# hall_sensor_final_displayv5.net
KiCad netlist of a schematic drawn in EAGLE
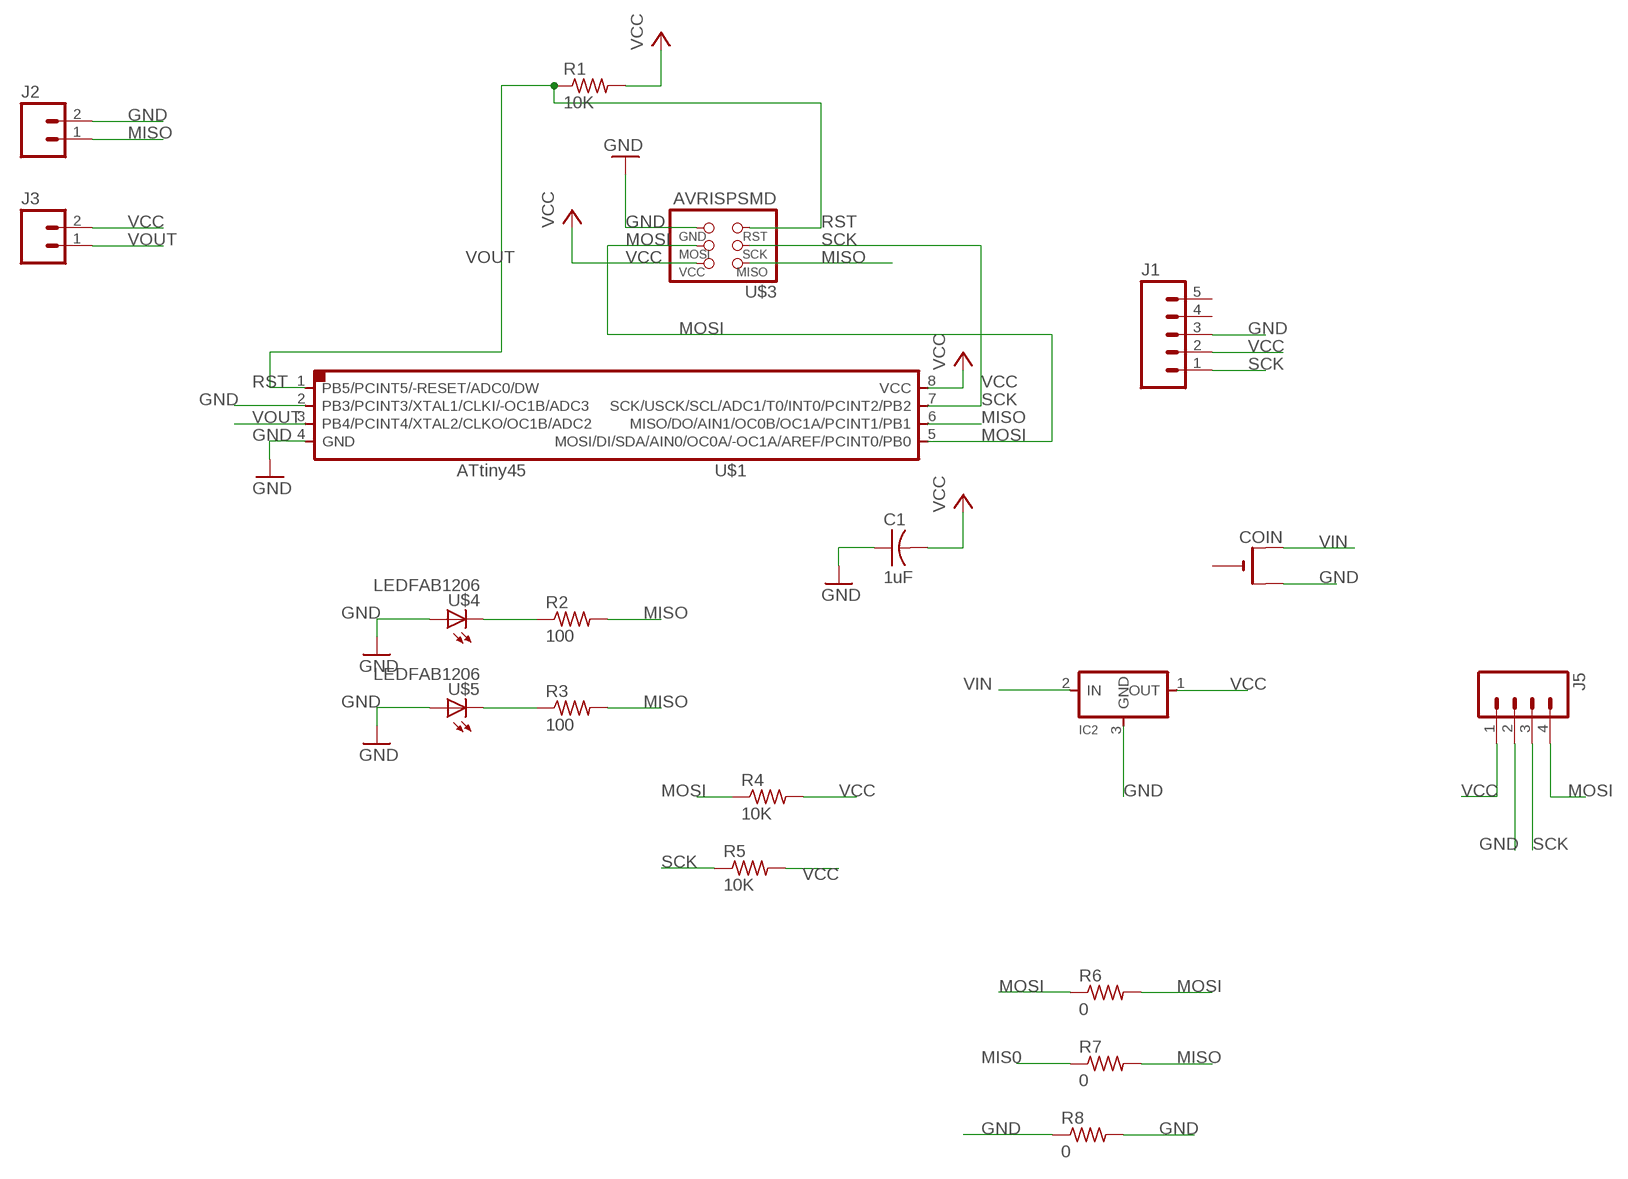
[diagram p0: schematic, sheet 1]

(export (version "E")
  (design (tool "Eeschema 10.0.6"))
  (components
    (comp (ref "C1")
      (value "1uF")
      (footprint "eagle-import:C1206FAB")
      (libsource (lib "eagle-import") (part "CAP-US1206FAB"))
    )
    (comp (ref "COIN")
      (value "CR2032THM")
      (footprint "eagle-import:CR2032-THRU")
      (libsource (lib "eagle-import") (part "CR2032THM"))
    )
    (comp (ref "IC2")
      (value "REGULATORSOT23")
      (footprint "eagle-import:SOT23")
      (libsource (lib "eagle-import") (part "REGULATORSOT23"))
    )
    (comp (ref "J1")
      (value "M05LOCK")
      (footprint "eagle-import:1X05_LOCK")
      (libsource (lib "eagle-import") (part "M05LOCK"))
    )
    (comp (ref "J2")
      (value "M02POLAR_LOCK")
      (footprint "eagle-import:MOLEX-1X2_LOCK")
      (libsource (lib "eagle-import") (part "M02POLAR_LOCK"))
    )
    (comp (ref "J3")
      (value "M02POLAR_LOCK")
      (footprint "eagle-import:MOLEX-1X2_LOCK")
      (libsource (lib "eagle-import") (part "M02POLAR_LOCK"))
    )
    (comp (ref "J5")
      (value "M04LOCK")
      (footprint "eagle-import:1X04_LOCK")
      (libsource (lib "eagle-import") (part "M04LOCK"))
    )
    (comp (ref "R1")
      (value "10K")
      (footprint "eagle-import:R1206FAB")
      (libsource (lib "eagle-import") (part "RES-US1206FAB"))
    )
    (comp (ref "R2")
      (value "100")
      (footprint "eagle-import:R1206FAB")
      (libsource (lib "eagle-import") (part "RES-US1206FAB"))
    )
    (comp (ref "R3")
      (value "100")
      (footprint "eagle-import:R1206FAB")
      (libsource (lib "eagle-import") (part "RES-US1206FAB"))
    )
    (comp (ref "R4")
      (value "10K")
      (footprint "eagle-import:R1206FAB")
      (libsource (lib "eagle-import") (part "RES-US1206FAB"))
    )
    (comp (ref "R5")
      (value "10K")
      (footprint "eagle-import:R1206FAB")
      (libsource (lib "eagle-import") (part "RES-US1206FAB"))
    )
    (comp (ref "R6")
      (value "0")
      (footprint "eagle-import:R1206FAB")
      (libsource (lib "eagle-import") (part "RES-US1206FAB"))
    )
    (comp (ref "R7")
      (value "0")
      (footprint "eagle-import:R1206FAB")
      (libsource (lib "eagle-import") (part "RES-US1206FAB"))
    )
    (comp (ref "R8")
      (value "0")
      (footprint "eagle-import:R1206FAB")
      (libsource (lib "eagle-import") (part "RES-US1206FAB"))
    )
    (comp (ref "U$1")
      (value "ATTINY45SI")
      (footprint "eagle-import:SOIC8")
      (libsource (lib "eagle-import") (part "ATTINY45SI"))
    )
    (comp (ref "U$3")
      (value "AVRISPSMD")
      (footprint "eagle-import:2X03SMD")
      (libsource (lib "eagle-import") (part "AVRISPSMD"))
    )
    (comp (ref "U$4")
      (value "LEDFAB1206")
      (footprint "eagle-import:LED1206FAB")
      (libsource (lib "eagle-import") (part "LEDFAB1206"))
    )
    (comp (ref "U$5")
      (value "LEDFAB1206")
      (footprint "eagle-import:LED1206FAB")
      (libsource (lib "eagle-import") (part "LEDFAB1206"))
    )
  )
  (nets
    (net (code "1") (name "/MIS0") (class "Default")
      (node (ref "R7") (pin "1") (pinfunction "1_1") (pintype "passive"))
    )
    (net (code "2") (name "/MISO") (class "Default")
      (node (ref "J2") (pin "1") (pinfunction "1_1") (pintype "passive"))
      (node (ref "R2") (pin "2") (pinfunction "2_2") (pintype "passive"))
      (node (ref "R3") (pin "2") (pinfunction "2_2") (pintype "passive"))
      (node (ref "R7") (pin "2") (pinfunction "2_2") (pintype "passive"))
      (node (ref "U$1") (pin "6") (pinfunction "MISO/DO/AIN1/OC0B/OC1A/PCINT1/PB1_6") (pintype "bidirectional"))
      (node (ref "U$3") (pin "1") (pinfunction "MISO_1") (pintype "passive"))
    )
    (net (code "3") (name "/MOSI") (class "Default")
      (node (ref "J5") (pin "4") (pinfunction "4_4") (pintype "passive"))
      (node (ref "R4") (pin "1") (pinfunction "1_1") (pintype "passive"))
      (node (ref "R6") (pin "1") (pinfunction "1_1") (pintype "passive"))
      (node (ref "R6") (pin "2") (pinfunction "2_2") (pintype "passive"))
      (node (ref "U$1") (pin "5") (pinfunction "MOSI/DI/SDA/AIN0/OC0A/-OC1A/AREF/PCINT0/PB0_5") (pintype "bidirectional"))
      (node (ref "U$3") (pin "4") (pinfunction "MOSI_4") (pintype "passive"))
    )
    (net (code "4") (name "/RST") (class "Default")
      (node (ref "R1") (pin "1") (pinfunction "1_1") (pintype "passive"))
      (node (ref "U$1") (pin "1") (pinfunction "PB5/PCINT5/-RESET/ADC0/DW_1") (pintype "bidirectional"))
      (node (ref "U$3") (pin "5") (pinfunction "RST_5") (pintype "passive"))
    )
    (net (code "5") (name "/SCK") (class "Default")
      (node (ref "J1") (pin "1") (pinfunction "1_1") (pintype "passive"))
      (node (ref "J5") (pin "3") (pinfunction "3_3") (pintype "passive"))
      (node (ref "R5") (pin "1") (pinfunction "1_1") (pintype "passive"))
      (node (ref "U$1") (pin "7") (pinfunction "SCK/USCK/SCL/ADC1/T0/INT0/PCINT2/PB2_7") (pintype "bidirectional"))
      (node (ref "U$3") (pin "3") (pinfunction "SCK_3") (pintype "passive"))
    )
    (net (code "6") (name "/VIN") (class "Default")
      (node (ref "COIN") (pin "+1") (pinfunction "+_+1") (pintype "passive"))
      (node (ref "IC2") (pin "2") (pinfunction "IN_2") (pintype "bidirectional"))
    )
    (net (code "7") (name "/VOUT") (class "Default")
      (node (ref "J3") (pin "1") (pinfunction "1_1") (pintype "passive"))
      (node (ref "U$1") (pin "3") (pinfunction "PB4/PCINT4/XTAL2/CLKO/OC1B/ADC2_3") (pintype "bidirectional"))
    )
    (net (code "8") (name "GND") (class "Default")
      (node (ref "C1") (pin "1") (pinfunction "1_1") (pintype "passive"))
      (node (ref "COIN") (pin "+2") (pinfunction "+1_+2") (pintype "passive"))
      (node (ref "IC2") (pin "3") (pinfunction "GND_3") (pintype "bidirectional"))
      (node (ref "J1") (pin "3") (pinfunction "3_3") (pintype "passive"))
      (node (ref "J2") (pin "2") (pinfunction "2_2") (pintype "passive"))
      (node (ref "J5") (pin "2") (pinfunction "2_2") (pintype "passive"))
      (node (ref "R8") (pin "1") (pinfunction "1_1") (pintype "passive"))
      (node (ref "R8") (pin "2") (pinfunction "2_2") (pintype "passive"))
      (node (ref "U$1") (pin "2") (pinfunction "PB3/PCINT3/XTAL1/CLKI/-OC1B/ADC3_2") (pintype "bidirectional"))
      (node (ref "U$1") (pin "4") (pinfunction "GND_4") (pintype "bidirectional"))
      (node (ref "U$3") (pin "6") (pinfunction "GND_6") (pintype "passive"))
      (node (ref "U$4") (pin "1") (pinfunction "A_1") (pintype "passive"))
      (node (ref "U$5") (pin "1") (pinfunction "A_1") (pintype "passive"))
    )
    (net (code "9") (name "Net-(U$4-C)") (class "Default")
      (node (ref "R2") (pin "1") (pinfunction "1_1") (pintype "passive"))
      (node (ref "U$4") (pin "2") (pinfunction "C_2") (pintype "passive"))
    )
    (net (code "10") (name "Net-(U$5-C)") (class "Default")
      (node (ref "R3") (pin "1") (pinfunction "1_1") (pintype "passive"))
      (node (ref "U$5") (pin "2") (pinfunction "C_2") (pintype "passive"))
    )
    (net (code "11") (name "VCC") (class "Default")
      (node (ref "C1") (pin "2") (pinfunction "2_2") (pintype "passive"))
      (node (ref "IC2") (pin "1") (pinfunction "OUT_1") (pintype "bidirectional"))
      (node (ref "J1") (pin "2") (pinfunction "2_2") (pintype "passive"))
      (node (ref "J3") (pin "2") (pinfunction "2_2") (pintype "passive"))
      (node (ref "J5") (pin "1") (pinfunction "1_1") (pintype "passive"))
      (node (ref "R1") (pin "2") (pinfunction "2_2") (pintype "passive"))
      (node (ref "R4") (pin "2") (pinfunction "2_2") (pintype "passive"))
      (node (ref "R5") (pin "2") (pinfunction "2_2") (pintype "passive"))
      (node (ref "U$1") (pin "8") (pinfunction "VCC_8") (pintype "bidirectional"))
      (node (ref "U$3") (pin "2") (pinfunction "VCC_2") (pintype "passive"))
    )
    (net (code "12") (name "unconnected-(COIN-Pad-)") (class "Default")
      (node (ref "COIN") (pin "-") (pinfunction "-_-") (pintype "passive"))
    )
    (net (code "13") (name "unconnected-(J1-Pad4)") (class "Default")
      (node (ref "J1") (pin "4") (pinfunction "4_4") (pintype "passive"))
    )
    (net (code "14") (name "unconnected-(J1-Pad5)") (class "Default")
      (node (ref "J1") (pin "5") (pinfunction "5_5") (pintype "passive"))
    )
  )
)
